# Sensing_Phase1.net
KiCad netlist of a schematic drawn in Altium Designer
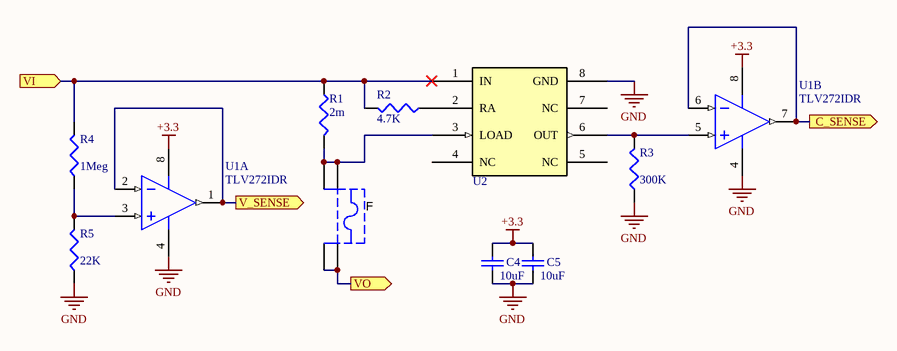
[diagram p0: Sensing_Phase1.SchDoc]

(export (version "E")
  (design (tool "Eeschema 10.0.6"))
  (components
    (comp (ref "C4")
      (value "10uF")
      (footprint "1608[0603]")
      (description "Capacitor (Semiconductor SIM Model)")
      (fields (field (name "Comment") "Cap Semi") (field (name "PUBLISHER") "Altium Limited"))
      (libsource (lib "Miscellaneous Devices") (part "Cap Semi"))
    )
    (comp (ref "C5")
      (value "10uF")
      (footprint "1608[0603]")
      (description "Capacitor (Semiconductor SIM Model)")
      (fields (field (name "Comment") "Cap Semi") (field (name "PUBLISHER") "Altium Limited"))
      (libsource (lib "Miscellaneous Devices") (part "Cap Semi"))
    )
    (comp (ref "F")
      (value "3568")
      (footprint "KSTN-3568_V")
      (description "Fuse Holder, 20 A, 500 V, -50 to 145 degC, 4-Pin THD, RoHS")
      (fields (field (name "MANUFACTURER") "Keystone"))
      (libsource (lib "FEV-60_Lib") (part "CMP-2000-05464-1"))
    )
    (comp (ref "R1")
      (value "2m")
      (footprint "Res_2512")
      (description "Resistor")
      (fields (field (name "Comment") "Res2512") (field (name "PUBLISHER") "Altium Limited"))
      (libsource (lib "FEV-60_Lib") (part "Res2512"))
    )
    (comp (ref "R2")
      (value "4.7K")
      (footprint "J1-0603")
      (description "Resistor")
      (fields (field (name "Comment") "Res3") (field (name "PUBLISHER") "Altium Limited"))
      (libsource (lib "Miscellaneous Devices") (part "Res3"))
    )
    (comp (ref "R3")
      (value "300K")
      (footprint "J1-0603")
      (description "Resistor")
      (fields (field (name "Comment") "Res3") (field (name "PUBLISHER") "Altium Limited"))
      (libsource (lib "Miscellaneous Devices") (part "Res3"))
    )
    (comp (ref "R4")
      (value "1Meg")
      (footprint "J1-0603")
      (description "Resistor")
      (fields (field (name "Comment") "Res3") (field (name "PUBLISHER") "Altium Limited"))
      (libsource (lib "Miscellaneous Devices") (part "Res3"))
    )
    (comp (ref "R5")
      (value "22K")
      (footprint "J1-0603")
      (description "Resistor")
      (fields (field (name "Comment") "Res3") (field (name "PUBLISHER") "Altium Limited"))
      (libsource (lib "Miscellaneous Devices") (part "Res3"))
    )
    (comp (ref "U1")
      (value "TLV272IDR")
      (footprint "D0008A_N")
      (fields (field (name "MANUFACTURER") "Texas Instruments"))
      (libsource (lib "FEV-60_Lib") (part "CMP-0272-02013-3"))
    )
    (comp (ref "U2")
      (value "HV7802")
      (footprint "HV7802")
      (description "High Side Current Monitor\r\n8V to 450V\r\nConfigurable Output")
      (libsource (lib "FEV-60_Lib") (part "HV7802"))
    )
  )
  (nets
    (net (code "1") (name "+3.3") (class "Default")
      (node (ref "C4") (pin "1") (pinfunction "1_1") (pintype "passive"))
      (node (ref "C5") (pin "1") (pinfunction "1_1") (pintype "passive"))
      (node (ref "U1") (pin "8") (pinfunction "VDD_8") (pintype "power_in"))
    )
    (net (code "2") (name "/C_SENSE") (class "Default")
      (node (ref "U1") (pin "6") (pinfunction "IN2-_6") (pintype "input"))
      (node (ref "U1") (pin "7") (pinfunction "OUT2_7") (pintype "output"))
    )
    (net (code "3") (name "/VI") (class "Default")
      (node (ref "R1") (pin "1") (pinfunction "1_1") (pintype "passive"))
      (node (ref "R2") (pin "2") (pinfunction "2_2") (pintype "passive"))
      (node (ref "R4") (pin "2") (pinfunction "2_2") (pintype "passive"))
      (node (ref "U2") (pin "1") (pinfunction "IN_1") (pintype "power_in"))
    )
    (net (code "4") (name "/VO") (class "Default")
      (node (ref "F") (pin "3") (pinfunction "3_3") (pintype "passive"))
      (node (ref "F") (pin "4") (pinfunction "4_4") (pintype "passive"))
    )
    (net (code "5") (name "/V_SENSE") (class "Default")
      (node (ref "U1") (pin "1") (pinfunction "OUT1_1") (pintype "output"))
      (node (ref "U1") (pin "2") (pinfunction "IN1-_2") (pintype "input"))
    )
    (net (code "6") (name "GND") (class "Default")
      (node (ref "C4") (pin "2") (pinfunction "2_2") (pintype "passive"))
      (node (ref "C5") (pin "2") (pinfunction "2_2") (pintype "passive"))
      (node (ref "R3") (pin "1") (pinfunction "1_1") (pintype "passive"))
      (node (ref "R5") (pin "1") (pinfunction "1_1") (pintype "passive"))
      (node (ref "U1") (pin "4") (pinfunction "GND_4") (pintype "power_in"))
      (node (ref "U2") (pin "8") (pinfunction "GND_8") (pintype "power_in"))
    )
    (net (code "7") (name "Net-(U1A-IN1+)") (class "Default")
      (node (ref "R4") (pin "1") (pinfunction "1_1") (pintype "passive"))
      (node (ref "R5") (pin "2") (pinfunction "2_2") (pintype "passive"))
      (node (ref "U1") (pin "3") (pinfunction "IN1+_3") (pintype "input"))
    )
    (net (code "8") (name "Net-(U1B-IN2+)") (class "Default")
      (node (ref "R3") (pin "2") (pinfunction "2_2") (pintype "passive"))
      (node (ref "U1") (pin "5") (pinfunction "IN2+_5") (pintype "input"))
      (node (ref "U2") (pin "6") (pinfunction "OUT_6") (pintype "output"))
    )
    (net (code "9") (name "Net-(U2-LOAD)") (class "Default")
      (node (ref "F") (pin "1") (pinfunction "1_1") (pintype "passive"))
      (node (ref "F") (pin "2") (pinfunction "2_2") (pintype "passive"))
      (node (ref "R1") (pin "2") (pinfunction "2_2") (pintype "passive"))
      (node (ref "U2") (pin "3") (pinfunction "LOAD_3") (pintype "input"))
    )
    (net (code "10") (name "Net-(U2-RA)") (class "Default")
      (node (ref "R2") (pin "1") (pinfunction "1_1") (pintype "passive"))
      (node (ref "U2") (pin "2") (pinfunction "RA_2") (pintype "passive"))
    )
    (net (code "11") (name "unconnected-(U2-NC-Pad4)") (class "Default")
      (node (ref "U2") (pin "4") (pinfunction "NC_4") (pintype "passive"))
    )
    (net (code "12") (name "unconnected-(U2-NC-Pad5)") (class "Default")
      (node (ref "U2") (pin "5") (pinfunction "NC_5") (pintype "passive"))
    )
    (net (code "13") (name "unconnected-(U2-NC-Pad7)") (class "Default")
      (node (ref "U2") (pin "7") (pinfunction "NC_7") (pintype "passive"))
    )
  )
)
